# H_bridge_circuit.net
KiCad netlist of a schematic drawn in Altium Designer
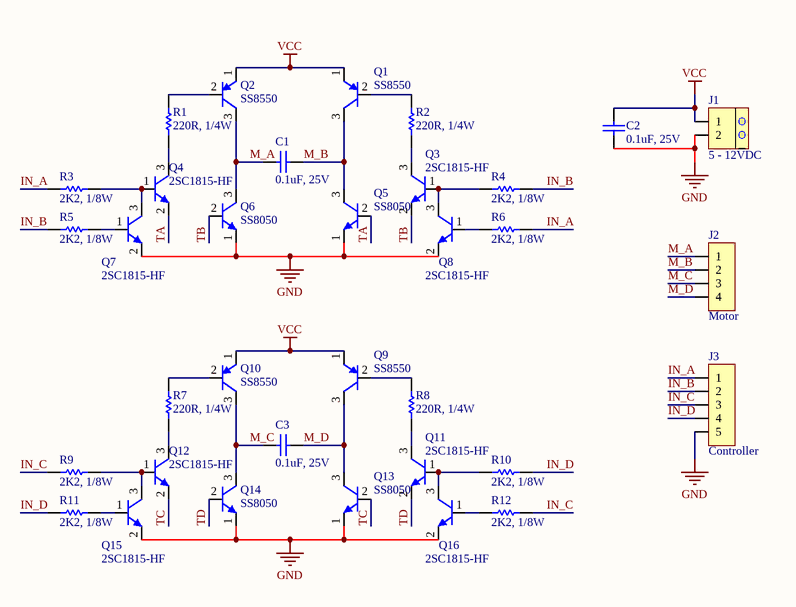
[diagram p0: H bridge circuit.SchDoc]

(export (version "E")
  (design (tool "Eeschema 10.0.6"))
  (components
    (comp (ref "C1")
      (value "0.1uF, 25V")
      (footprint "C0_1uF")
      (description "CAP Y5P CAPNTO 0.1uF 25V 20%")
      (fields (field (name "Comment") "5WF104MABAA"))
      (libsource (lib "Sau_Capacitors") (part "5WF104MABAA"))
    )
    (comp (ref "C2")
      (value "0.1uF, 25V")
      (footprint "C0_1uF")
      (description "CAP Y5P CAPNTO 0.1uF 25V 20%")
      (fields (field (name "Comment") "5WF104MABAA"))
      (libsource (lib "Sau_Capacitors") (part "5WF104MABAA"))
    )
    (comp (ref "C3")
      (value "0.1uF, 25V")
      (footprint "C0_1uF")
      (description "CAP Y5P CAPNTO 0.1uF 25V 20%")
      (fields (field (name "Comment") "5WF104MABAA"))
      (libsource (lib "Sau_Capacitors") (part "5WF104MABAA"))
    )
    (comp (ref "J1")
      (value "5 - 12VDC")
      (footprint "CON2")
      (description "Terminal Block 2 Poles 5.08mm Blue")
      (fields (field (name "Comment") "OSTTC-02-2162"))
      (libsource (lib "Sau_Connectors") (part "OSTTC-02-2162"))
    )
    (comp (ref "J2")
      (value "Motor")
      (footprint "Header_4")
      (description "Male Header 04 Pin 2.54mm Straight")
      (fields (field (name "Comment") "2012-254-1x04-SG"))
      (libsource (lib "Sau_Connectors") (part "2012-254-1x04-SG"))
    )
    (comp (ref "J3")
      (value "Controller")
      (footprint "Header_5")
      (description "Male Header 05 Pin 2.54mm Straight")
      (fields (field (name "Comment") "2012-254-1x05-SG"))
      (libsource (lib "Sau_Connectors") (part "2012-254-1x05-SG"))
    )
    (comp (ref "Q1")
      (value "SS8550")
      (footprint "SS8550")
      (description "Trans PNP -25V -1.5A TO-92")
      (libsource (lib "Sau_Transistors") (part "SS8550"))
    )
    (comp (ref "Q2")
      (value "SS8550")
      (footprint "SS8550")
      (description "Trans PNP -25V -1.5A TO-92")
      (libsource (lib "Sau_Transistors") (part "SS8550"))
    )
    (comp (ref "Q3")
      (value "2SC1815-HF")
      (footprint "2SC1815-HF")
      (description "Trans NPN 50V 150mA SOT-23")
      (libsource (lib "Sau_Transistors") (part "2SC1815-HF"))
    )
    (comp (ref "Q4")
      (value "2SC1815-HF")
      (footprint "2SC1815-HF")
      (description "Trans NPN 50V 150mA SOT-23")
      (libsource (lib "Sau_Transistors") (part "2SC1815-HF"))
    )
    (comp (ref "Q5")
      (value "SS8050")
      (footprint "SS8050")
      (description "Trans NPN 25V 1.5A TO-92")
      (libsource (lib "Sau_Transistors") (part "SS8050"))
    )
    (comp (ref "Q6")
      (value "SS8050")
      (footprint "SS8050")
      (description "Trans NPN 25V 1.5A TO-92")
      (libsource (lib "Sau_Transistors") (part "SS8050"))
    )
    (comp (ref "Q7")
      (value "2SC1815-HF")
      (footprint "2SC1815-HF")
      (description "Trans NPN 50V 150mA SOT-23")
      (libsource (lib "Sau_Transistors") (part "2SC1815-HF"))
    )
    (comp (ref "Q8")
      (value "2SC1815-HF")
      (footprint "2SC1815-HF")
      (description "Trans NPN 50V 150mA SOT-23")
      (libsource (lib "Sau_Transistors") (part "2SC1815-HF"))
    )
    (comp (ref "Q9")
      (value "SS8550")
      (footprint "SS8550")
      (description "Trans PNP -25V -1.5A TO-92")
      (libsource (lib "Sau_Transistors") (part "SS8550"))
    )
    (comp (ref "Q10")
      (value "SS8550")
      (footprint "SS8550")
      (description "Trans PNP -25V -1.5A TO-92")
      (libsource (lib "Sau_Transistors") (part "SS8550"))
    )
    (comp (ref "Q11")
      (value "2SC1815-HF")
      (footprint "2SC1815-HF")
      (description "Trans NPN 50V 150mA SOT-23")
      (libsource (lib "Sau_Transistors") (part "2SC1815-HF"))
    )
    (comp (ref "Q12")
      (value "2SC1815-HF")
      (footprint "2SC1815-HF")
      (description "Trans NPN 50V 150mA SOT-23")
      (libsource (lib "Sau_Transistors") (part "2SC1815-HF"))
    )
    (comp (ref "Q13")
      (value "SS8050")
      (footprint "SS8050")
      (description "Trans NPN 25V 1.5A TO-92")
      (libsource (lib "Sau_Transistors") (part "SS8050"))
    )
    (comp (ref "Q14")
      (value "SS8050")
      (footprint "SS8050")
      (description "Trans NPN 25V 1.5A TO-92")
      (libsource (lib "Sau_Transistors") (part "SS8050"))
    )
    (comp (ref "Q15")
      (value "2SC1815-HF")
      (footprint "2SC1815-HF")
      (description "Trans NPN 50V 150mA SOT-23")
      (libsource (lib "Sau_Transistors") (part "2SC1815-HF"))
    )
    (comp (ref "Q16")
      (value "2SC1815-HF")
      (footprint "2SC1815-HF")
      (description "Trans NPN 50V 150mA SOT-23")
      (libsource (lib "Sau_Transistors") (part "2SC1815-HF"))
    )
    (comp (ref "R1")
      (value "220R, 1/4W")
      (footprint "RESC2012L")
      (description "RES CF AXIAL-0.3 5% 1/4W 220R")
      (fields (field (name "Comment") "CF1/4W220RJ25"))
      (libsource (lib "Sau_Resistors") (part "CF1/4W220RJ25"))
    )
    (comp (ref "R2")
      (value "220R, 1/4W")
      (footprint "RESC2012L")
      (description "RES CF AXIAL-0.3 5% 1/4W 220R")
      (fields (field (name "Comment") "CF1/4W220RJ25"))
      (libsource (lib "Sau_Resistors") (part "CF1/4W220RJ25"))
    )
    (comp (ref "R3")
      (value "2K2, 1/8W")
      (footprint "RESC2012L")
      (description "RES CR 0805 5% 1/8W 2K2")
      (fields (field (name "Comment") "CR05JL7-2K2"))
      (libsource (lib "Sau_Resistors") (part "CR05JL7-2K2"))
    )
    (comp (ref "R4")
      (value "2K2, 1/8W")
      (footprint "RESC2012L")
      (description "RES CR 0805 5% 1/8W 2K2")
      (fields (field (name "Comment") "CR05JL7-2K2"))
      (libsource (lib "Sau_Resistors") (part "CR05JL7-2K2"))
    )
    (comp (ref "R5")
      (value "2K2, 1/8W")
      (footprint "RESC2012L")
      (description "RES CR 0805 5% 1/8W 2K2")
      (fields (field (name "Comment") "CR05JL7-2K2"))
      (libsource (lib "Sau_Resistors") (part "CR05JL7-2K2"))
    )
    (comp (ref "R6")
      (value "2K2, 1/8W")
      (footprint "RESC2012L")
      (description "RES CR 0805 5% 1/8W 2K2")
      (fields (field (name "Comment") "CR05JL7-2K2"))
      (libsource (lib "Sau_Resistors") (part "CR05JL7-2K2"))
    )
    (comp (ref "R7")
      (value "220R, 1/4W")
      (footprint "RESC2012L")
      (description "RES CF AXIAL-0.3 5% 1/4W 220R")
      (fields (field (name "Comment") "CF1/4W220RJ25"))
      (libsource (lib "Sau_Resistors") (part "CF1/4W220RJ25"))
    )
    (comp (ref "R8")
      (value "220R, 1/4W")
      (footprint "RESC2012L")
      (description "RES CF AXIAL-0.3 5% 1/4W 220R")
      (fields (field (name "Comment") "CF1/4W220RJ25"))
      (libsource (lib "Sau_Resistors") (part "CF1/4W220RJ25"))
    )
    (comp (ref "R9")
      (value "2K2, 1/8W")
      (footprint "RESC2012L")
      (description "RES CR 0805 5% 1/8W 2K2")
      (fields (field (name "Comment") "CR05JL7-2K2"))
      (libsource (lib "Sau_Resistors") (part "CR05JL7-2K2"))
    )
    (comp (ref "R10")
      (value "2K2, 1/8W")
      (footprint "RESC2012L")
      (description "RES CR 0805 5% 1/8W 2K2")
      (fields (field (name "Comment") "CR05JL7-2K2"))
      (libsource (lib "Sau_Resistors") (part "CR05JL7-2K2"))
    )
    (comp (ref "R11")
      (value "2K2, 1/8W")
      (footprint "RESC2012L")
      (description "RES CR 0805 5% 1/8W 2K2")
      (fields (field (name "Comment") "CR05JL7-2K2"))
      (libsource (lib "Sau_Resistors") (part "CR05JL7-2K2"))
    )
    (comp (ref "R12")
      (value "2K2, 1/8W")
      (footprint "RESC2012L")
      (description "RES CR 0805 5% 1/8W 2K2")
      (fields (field (name "Comment") "CR05JL7-2K2"))
      (libsource (lib "Sau_Resistors") (part "CR05JL7-2K2"))
    )
  )
  (nets
    (net (code "1") (name "/IN_A") (class "Default")
      (node (ref "J3") (pin "1") (pinfunction "1_1") (pintype "passive"))
      (node (ref "R3") (pin "1") (pinfunction "1_1") (pintype "passive"))
      (node (ref "R6") (pin "2") (pinfunction "2_2") (pintype "passive"))
    )
    (net (code "2") (name "/IN_B") (class "Default")
      (node (ref "J3") (pin "2") (pinfunction "2_2") (pintype "passive"))
      (node (ref "R4") (pin "2") (pinfunction "2_2") (pintype "passive"))
      (node (ref "R5") (pin "1") (pinfunction "1_1") (pintype "passive"))
    )
    (net (code "3") (name "/IN_C") (class "Default")
      (node (ref "J3") (pin "3") (pinfunction "3_3") (pintype "passive"))
      (node (ref "R12") (pin "2") (pinfunction "2_2") (pintype "passive"))
      (node (ref "R9") (pin "1") (pinfunction "1_1") (pintype "passive"))
    )
    (net (code "4") (name "/IN_D") (class "Default")
      (node (ref "J3") (pin "4") (pinfunction "4_4") (pintype "passive"))
      (node (ref "R10") (pin "2") (pinfunction "2_2") (pintype "passive"))
      (node (ref "R11") (pin "1") (pinfunction "1_1") (pintype "passive"))
    )
    (net (code "5") (name "/M_A") (class "Default")
      (node (ref "C1") (pin "1") (pinfunction "1_1") (pintype "passive"))
      (node (ref "J2") (pin "1") (pinfunction "1_1") (pintype "passive"))
      (node (ref "Q2") (pin "3") (pinfunction "C_3") (pintype "passive"))
      (node (ref "Q6") (pin "3") (pinfunction "C_3") (pintype "passive"))
    )
    (net (code "6") (name "/M_B") (class "Default")
      (node (ref "C1") (pin "2") (pinfunction "2_2") (pintype "passive"))
      (node (ref "J2") (pin "2") (pinfunction "2_2") (pintype "passive"))
      (node (ref "Q1") (pin "3") (pinfunction "C_3") (pintype "passive"))
      (node (ref "Q5") (pin "3") (pinfunction "C_3") (pintype "passive"))
    )
    (net (code "7") (name "/M_C") (class "Default")
      (node (ref "C3") (pin "1") (pinfunction "1_1") (pintype "passive"))
      (node (ref "J2") (pin "3") (pinfunction "3_3") (pintype "passive"))
      (node (ref "Q10") (pin "3") (pinfunction "C_3") (pintype "passive"))
      (node (ref "Q14") (pin "3") (pinfunction "C_3") (pintype "passive"))
    )
    (net (code "8") (name "/M_D") (class "Default")
      (node (ref "C3") (pin "2") (pinfunction "2_2") (pintype "passive"))
      (node (ref "J2") (pin "4") (pinfunction "4_4") (pintype "passive"))
      (node (ref "Q13") (pin "3") (pinfunction "C_3") (pintype "passive"))
      (node (ref "Q9") (pin "3") (pinfunction "C_3") (pintype "passive"))
    )
    (net (code "9") (name "/TA") (class "Default")
      (node (ref "Q4") (pin "2") (pinfunction "E_2") (pintype "passive"))
      (node (ref "Q5") (pin "2") (pinfunction "B_2") (pintype "passive"))
    )
    (net (code "10") (name "/TB") (class "Default")
      (node (ref "Q3") (pin "2") (pinfunction "E_2") (pintype "passive"))
      (node (ref "Q6") (pin "2") (pinfunction "B_2") (pintype "passive"))
    )
    (net (code "11") (name "/TC") (class "Default")
      (node (ref "Q12") (pin "2") (pinfunction "E_2") (pintype "passive"))
      (node (ref "Q13") (pin "2") (pinfunction "B_2") (pintype "passive"))
    )
    (net (code "12") (name "/TD") (class "Default")
      (node (ref "Q11") (pin "2") (pinfunction "E_2") (pintype "passive"))
      (node (ref "Q14") (pin "2") (pinfunction "B_2") (pintype "passive"))
    )
    (net (code "13") (name "GND") (class "Default")
      (node (ref "C2") (pin "1") (pinfunction "1_1") (pintype "passive"))
      (node (ref "J1") (pin "2") (pinfunction "2_2") (pintype "passive"))
      (node (ref "J3") (pin "5") (pinfunction "5_5") (pintype "passive"))
      (node (ref "Q13") (pin "1") (pinfunction "E_1") (pintype "passive"))
      (node (ref "Q14") (pin "1") (pinfunction "E_1") (pintype "passive"))
      (node (ref "Q15") (pin "2") (pinfunction "E_2") (pintype "passive"))
      (node (ref "Q16") (pin "2") (pinfunction "E_2") (pintype "passive"))
      (node (ref "Q5") (pin "1") (pinfunction "E_1") (pintype "passive"))
      (node (ref "Q6") (pin "1") (pinfunction "E_1") (pintype "passive"))
      (node (ref "Q7") (pin "2") (pinfunction "E_2") (pintype "passive"))
      (node (ref "Q8") (pin "2") (pinfunction "E_2") (pintype "passive"))
    )
    (net (code "14") (name "Net-(Q1-B)") (class "Default")
      (node (ref "Q1") (pin "2") (pinfunction "B_2") (pintype "passive"))
      (node (ref "R2") (pin "2") (pinfunction "2_2") (pintype "passive"))
    )
    (net (code "15") (name "Net-(Q2-B)") (class "Default")
      (node (ref "Q2") (pin "2") (pinfunction "B_2") (pintype "passive"))
      (node (ref "R1") (pin "2") (pinfunction "2_2") (pintype "passive"))
    )
    (net (code "16") (name "Net-(Q3-B)") (class "Default")
      (node (ref "Q3") (pin "1") (pinfunction "B_1") (pintype "passive"))
      (node (ref "Q8") (pin "3") (pinfunction "C_3") (pintype "passive"))
      (node (ref "R4") (pin "1") (pinfunction "1_1") (pintype "passive"))
    )
    (net (code "17") (name "Net-(Q3-C)") (class "Default")
      (node (ref "Q3") (pin "3") (pinfunction "C_3") (pintype "passive"))
      (node (ref "R2") (pin "1") (pinfunction "1_1") (pintype "passive"))
    )
    (net (code "18") (name "Net-(Q4-B)") (class "Default")
      (node (ref "Q4") (pin "1") (pinfunction "B_1") (pintype "passive"))
      (node (ref "Q7") (pin "3") (pinfunction "C_3") (pintype "passive"))
      (node (ref "R3") (pin "2") (pinfunction "2_2") (pintype "passive"))
    )
    (net (code "19") (name "Net-(Q4-C)") (class "Default")
      (node (ref "Q4") (pin "3") (pinfunction "C_3") (pintype "passive"))
      (node (ref "R1") (pin "1") (pinfunction "1_1") (pintype "passive"))
    )
    (net (code "20") (name "Net-(Q7-B)") (class "Default")
      (node (ref "Q7") (pin "1") (pinfunction "B_1") (pintype "passive"))
      (node (ref "R5") (pin "2") (pinfunction "2_2") (pintype "passive"))
    )
    (net (code "21") (name "Net-(Q8-B)") (class "Default")
      (node (ref "Q8") (pin "1") (pinfunction "B_1") (pintype "passive"))
      (node (ref "R6") (pin "1") (pinfunction "1_1") (pintype "passive"))
    )
    (net (code "22") (name "Net-(Q9-B)") (class "Default")
      (node (ref "Q9") (pin "2") (pinfunction "B_2") (pintype "passive"))
      (node (ref "R8") (pin "2") (pinfunction "2_2") (pintype "passive"))
    )
    (net (code "23") (name "Net-(Q10-B)") (class "Default")
      (node (ref "Q10") (pin "2") (pinfunction "B_2") (pintype "passive"))
      (node (ref "R7") (pin "2") (pinfunction "2_2") (pintype "passive"))
    )
    (net (code "24") (name "Net-(Q11-B)") (class "Default")
      (node (ref "Q11") (pin "1") (pinfunction "B_1") (pintype "passive"))
      (node (ref "Q16") (pin "3") (pinfunction "C_3") (pintype "passive"))
      (node (ref "R10") (pin "1") (pinfunction "1_1") (pintype "passive"))
    )
    (net (code "25") (name "Net-(Q11-C)") (class "Default")
      (node (ref "Q11") (pin "3") (pinfunction "C_3") (pintype "passive"))
      (node (ref "R8") (pin "1") (pinfunction "1_1") (pintype "passive"))
    )
    (net (code "26") (name "Net-(Q12-B)") (class "Default")
      (node (ref "Q12") (pin "1") (pinfunction "B_1") (pintype "passive"))
      (node (ref "Q15") (pin "3") (pinfunction "C_3") (pintype "passive"))
      (node (ref "R9") (pin "2") (pinfunction "2_2") (pintype "passive"))
    )
    (net (code "27") (name "Net-(Q12-C)") (class "Default")
      (node (ref "Q12") (pin "3") (pinfunction "C_3") (pintype "passive"))
      (node (ref "R7") (pin "1") (pinfunction "1_1") (pintype "passive"))
    )
    (net (code "28") (name "Net-(Q15-B)") (class "Default")
      (node (ref "Q15") (pin "1") (pinfunction "B_1") (pintype "passive"))
      (node (ref "R11") (pin "2") (pinfunction "2_2") (pintype "passive"))
    )
    (net (code "29") (name "Net-(Q16-B)") (class "Default")
      (node (ref "Q16") (pin "1") (pinfunction "B_1") (pintype "passive"))
      (node (ref "R12") (pin "1") (pinfunction "1_1") (pintype "passive"))
    )
    (net (code "30") (name "VCC") (class "Default")
      (node (ref "C2") (pin "2") (pinfunction "2_2") (pintype "passive"))
      (node (ref "J1") (pin "1") (pinfunction "1_1") (pintype "passive"))
      (node (ref "Q1") (pin "1") (pinfunction "E_1") (pintype "passive"))
      (node (ref "Q10") (pin "1") (pinfunction "E_1") (pintype "passive"))
      (node (ref "Q2") (pin "1") (pinfunction "E_1") (pintype "passive"))
      (node (ref "Q9") (pin "1") (pinfunction "E_1") (pintype "passive"))
    )
  )
)
